# sheet1.net
KiCad netlist of a schematic drawn in Altium Designer
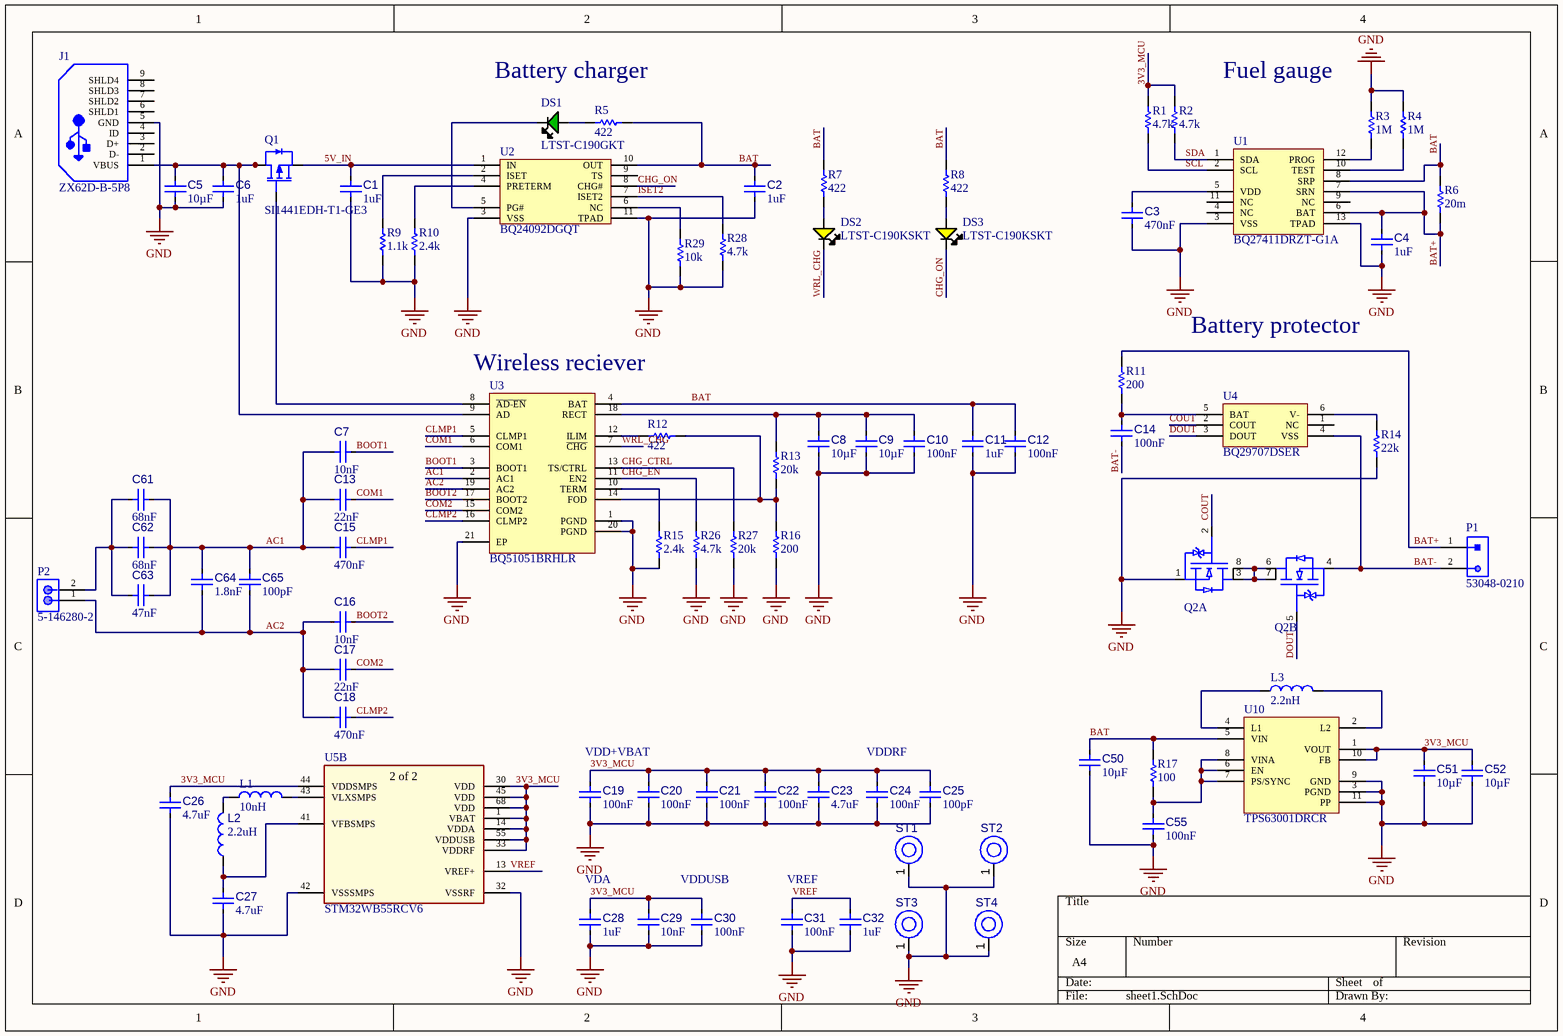
[diagram p0: sheet1.SchDoc]

(export (version "E")
  (design (tool "Eeschema 10.0.6"))
  (components
    (comp (ref "C1")
      (value "1uF")
      (footprint "0603-SMD-CAP")
      (fields
        (field (name "VOLTAGE") "25V")
        (field (name "TOLERANCE") "10%")
        (field (name "MFR. PART NO.") "C0603C105K3PACTU")
      )
      (libsource (lib "Budapest University of Technology and Economics") (part "CAP-NP-2"))
    )
    (comp (ref "C2")
      (value "1uF")
      (footprint "0603-SMD-CAP")
      (fields
        (field (name "VOLTAGE") "25V")
        (field (name "TOLERANCE") "10%")
        (field (name "MFR. PART NO.") "C0603C105K3PACTU")
      )
      (libsource (lib "Budapest University of Technology and Economics") (part "CAP-NP-2"))
    )
    (comp (ref "C3")
      (value "470nF")
      (footprint "CAPC0603(1608)100_L")
      (description "Chip Capacitor, 470nF +/-20%, 25V, 0603, Thickness 1 mm")
      (fields (field (name "TOLERANCE") "10%") (field (name "Comment") "Capacitor 470nF +/-20% 25V 0603"))
      (libsource (lib "Budapest University of Technology and Economics") (part "CAP-NP-2"))
    )
    (comp (ref "C4")
      (value "1uF")
      (footprint "0603-SMD-CAP")
      (fields
        (field (name "VOLTAGE") "25V")
        (field (name "TOLERANCE") "10%")
        (field (name "MFR. PART NO.") "C0603C105K3PACTU")
      )
      (libsource (lib "Budapest University of Technology and Economics") (part "CAP-NP-2"))
    )
    (comp (ref "C5")
      (value "10µF")
      (footprint "0603-SMD-CAP")
      (description "Chip Capacitor, 10µF +/-20%, 10V, 0603, Thickness 1 mm")
      (fields (field (name "TOLERANCE") "10%") (field (name "MFR. PART NO.") "0603ZD106KAT2A"))
      (libsource (lib "Budapest University of Technology and Economics") (part "CAP-NP-2"))
    )
    (comp (ref "C6")
      (value "1uF")
      (footprint "0603-SMD-CAP")
      (fields
        (field (name "VOLTAGE") "25V")
        (field (name "TOLERANCE") "10%")
        (field (name "MFR. PART NO.") "C0603C105K3PACTU")
      )
      (libsource (lib "Budapest University of Technology and Economics") (part "CAP-NP-2"))
    )
    (comp (ref "C7")
      (value "10nF")
      (footprint "0402-SMD-CAP")
      (description "Cap Ceramic 0.01uF 50V X7R 10% SMD 0402 125C Paper T/R")
      (fields (field (name "TOLERANCE") "10%") (field (name "VOLTAGE") "50V"))
      (libsource (lib "Budapest University of Technology and Economics") (part "CAP-NP-2"))
    )
    (comp (ref "C8")
      (value "10µF")
      (footprint "0603-SMD-CAP")
      (description "Chip Capacitor, 10µF +/-20%, 10V, 0603, Thickness 1 mm")
      (fields (field (name "TOLERANCE") "10%") (field (name "MFR. PART NO.") "0603ZD106KAT2A"))
      (libsource (lib "Budapest University of Technology and Economics") (part "CAP-NP-2"))
    )
    (comp (ref "C9")
      (value "10µF")
      (footprint "0603-SMD-CAP")
      (description "Chip Capacitor, 10µF +/-20%, 10V, 0603, Thickness 1 mm")
      (fields (field (name "TOLERANCE") "10%") (field (name "MFR. PART NO.") "0603ZD106KAT2A"))
      (libsource (lib "Budapest University of Technology and Economics") (part "CAP-NP-2"))
    )
    (comp (ref "C10")
      (value "100nF")
      (footprint "0402-SMD-CAP")
      (description "Chip Capacitor, 0.1 uF, +/- 5%, 16 V, 0402 (1005 Metric)")
      (fields (field (name "TOLERANCE") "5%") (field (name "MFR. PART NO.") "EMF105B7104MVHF"))
      (libsource (lib "Budapest University of Technology and Economics") (part "CAP-NP-2"))
    )
    (comp (ref "C11")
      (value "1uF")
      (footprint "0603-SMD-CAP")
      (fields
        (field (name "VOLTAGE") "25V")
        (field (name "TOLERANCE") "10%")
        (field (name "MFR. PART NO.") "C0603C105K3PACTU")
      )
      (libsource (lib "Budapest University of Technology and Economics") (part "CAP-NP-2"))
    )
    (comp (ref "C12")
      (value "100nF")
      (footprint "0402-SMD-CAP")
      (description "Chip Capacitor, 0.1 uF, +/- 5%, 16 V, 0402 (1005 Metric)")
      (fields (field (name "TOLERANCE") "5%") (field (name "MFR. PART NO.") "EMF105B7104MVHF"))
      (libsource (lib "Budapest University of Technology and Economics") (part "CAP-NP-2"))
    )
    (comp (ref "C13")
      (value "22nF")
      (footprint "0402-SMD-CAP")
      (description "0402 22 nF 25 V ±10 % Tolerance X7R SMT Multilayer Ceramic Capacitor")
      (fields (field (name "TOLERANCE") "10%") (field (name "MFR. PART NO.") "CC0402KRX7R8BB223"))
      (libsource (lib "Budapest University of Technology and Economics") (part "CAP-NP-2"))
    )
    (comp (ref "C14")
      (value "100nF")
      (footprint "0402-SMD-CAP")
      (description "Chip Capacitor, 0.1 uF, +/- 5%, 16 V, 0402 (1005 Metric)")
      (fields (field (name "TOLERANCE") "5%") (field (name "MFR. PART NO.") "EMF105B7104MVHF"))
      (libsource (lib "Budapest University of Technology and Economics") (part "CAP-NP-2"))
    )
    (comp (ref "C15")
      (value "470nF")
      (footprint "0402-SMD-CAP")
      (description "TDK         C1005X5R1E474K050BB            CERAMIC CAPACITOR, 0.47UF, 25V, X5R, 0402")
      (fields (field (name "MFR. PART NO.") "C1005X5R1E474K050BB") (field (name "VOLTAGE") "25V"))
      (libsource (lib "Budapest University of Technology and Economics") (part "CAP-NP-2"))
    )
    (comp (ref "C16")
      (value "10nF")
      (footprint "0402-SMD-CAP")
      (description "Cap Ceramic 0.01uF 50V X7R 10% SMD 0402 125C Paper T/R")
      (fields (field (name "TOLERANCE") "10%") (field (name "VOLTAGE") "50V"))
      (libsource (lib "Budapest University of Technology and Economics") (part "CAP-NP-2"))
    )
    (comp (ref "C17")
      (value "22nF")
      (footprint "0402-SMD-CAP")
      (description "0402 22 nF 25 V ±10 % Tolerance X7R SMT Multilayer Ceramic Capacitor")
      (fields (field (name "TOLERANCE") "10%") (field (name "MFR. PART NO.") "CC0402KRX7R8BB223"))
      (libsource (lib "Budapest University of Technology and Economics") (part "CAP-NP-2"))
    )
    (comp (ref "C18")
      (value "470nF")
      (footprint "0402-SMD-CAP")
      (description "TDK         C1005X5R1E474K050BB            CERAMIC CAPACITOR, 0.47UF, 25V, X5R, 0402")
      (fields (field (name "MFR. PART NO.") "C1005X5R1E474K050BB") (field (name "VOLTAGE") "25V"))
      (libsource (lib "Budapest University of Technology and Economics") (part "CAP-NP-2"))
    )
    (comp (ref "C19")
      (value "100nF")
      (footprint "0402-SMD-CAP")
      (description "Chip Capacitor, 0.1 uF, +/- 5%, 16 V, 0402 (1005 Metric)")
      (fields (field (name "TOLERANCE") "5%") (field (name "MFR. PART NO.") "EMF105B7104MVHF"))
      (libsource (lib "Budapest University of Technology and Economics") (part "CAP-NP-2"))
    )
    (comp (ref "C20")
      (value "100nF")
      (footprint "0402-SMD-CAP")
      (description "Chip Capacitor, 0.1 uF, +/- 5%, 16 V, 0402 (1005 Metric)")
      (fields (field (name "TOLERANCE") "5%") (field (name "MFR. PART NO.") "EMF105B7104MVHF"))
      (libsource (lib "Budapest University of Technology and Economics") (part "CAP-NP-2"))
    )
    (comp (ref "C21")
      (value "100nF")
      (footprint "0402-SMD-CAP")
      (description "Chip Capacitor, 0.1 uF, +/- 5%, 16 V, 0402 (1005 Metric)")
      (fields (field (name "TOLERANCE") "5%") (field (name "MFR. PART NO.") "EMF105B7104MVHF"))
      (libsource (lib "Budapest University of Technology and Economics") (part "CAP-NP-2"))
    )
    (comp (ref "C22")
      (value "100nF")
      (footprint "0402-SMD-CAP")
      (description "Chip Capacitor, 0.1 uF, +/- 5%, 16 V, 0402 (1005 Metric)")
      (fields (field (name "TOLERANCE") "5%") (field (name "MFR. PART NO.") "EMF105B7104MVHF"))
      (libsource (lib "Budapest University of Technology and Economics") (part "CAP-NP-2"))
    )
    (comp (ref "C23")
      (value "4.7uF")
      (footprint "0603-SMD-CAP")
      (fields
        (field (name "TOLERANCE") "10%")
        (field (name "VOLTAGE") "6.3V")
        (field (name "Comment") "C0603C475K9PACTU")
      )
      (libsource (lib "Budapest University of Technology and Economics") (part "CAP-NP-2"))
    )
    (comp (ref "C24")
      (value "100nF")
      (footprint "0402-SMD-CAP")
      (description "Chip Capacitor, 0.1 uF, +/- 5%, 16 V, 0402 (1005 Metric)")
      (fields (field (name "TOLERANCE") "5%") (field (name "MFR. PART NO.") "EMF105B7104MVHF"))
      (libsource (lib "Budapest University of Technology and Economics") (part "CAP-NP-2"))
    )
    (comp (ref "C25")
      (value "100pF")
      (footprint "0402-SMD-CAP")
      (description "Capacitor, Ceramic; 100pf; Chip; Case 0402; Npo; +/-5%; 50wvdc; Smd; 2.5% Df; Tr")
      (fields (field (name "VOLTAGE") "50V") (field (name "TOLERANCE") "5%"))
      (libsource (lib "Budapest University of Technology and Economics") (part "CAP-NP-2"))
    )
    (comp (ref "C26")
      (value "4.7uF")
      (footprint "0603-SMD-CAP")
      (fields
        (field (name "TOLERANCE") "10%")
        (field (name "VOLTAGE") "6.3V")
        (field (name "Comment") "C0603C475K9PACTU")
      )
      (libsource (lib "Budapest University of Technology and Economics") (part "CAP-NP-2"))
    )
    (comp (ref "C27")
      (value "4.7uF")
      (footprint "0603-SMD-CAP")
      (fields
        (field (name "TOLERANCE") "10%")
        (field (name "VOLTAGE") "6.3V")
        (field (name "Comment") "C0603C475K9PACTU")
      )
      (libsource (lib "Budapest University of Technology and Economics") (part "CAP-NP-2"))
    )
    (comp (ref "C28")
      (value "1uF")
      (footprint "0603-SMD-CAP")
      (fields
        (field (name "VOLTAGE") "25V")
        (field (name "TOLERANCE") "10%")
        (field (name "MFR. PART NO.") "C0603C105K3PACTU")
      )
      (libsource (lib "Budapest University of Technology and Economics") (part "CAP-NP-2"))
    )
    (comp (ref "C29")
      (value "10nF")
      (footprint "0402-SMD-CAP")
      (description "CAP CER 10000PF 16V X7R 0402")
      (fields (field (name "MFR. PART NO.") "CC0402KRX7R7BB103") (field (name "TOLERANCE") "10%"))
      (libsource (lib "Budapest University of Technology and Economics") (part "CAP-NP-2"))
    )
    (comp (ref "C30")
      (value "100nF")
      (footprint "0402-SMD-CAP")
      (description "Chip Capacitor, 0.1 uF, +/- 5%, 16 V, 0402 (1005 Metric)")
      (fields (field (name "TOLERANCE") "5%") (field (name "MFR. PART NO.") "EMF105B7104MVHF"))
      (libsource (lib "Budapest University of Technology and Economics") (part "CAP-NP-2"))
    )
    (comp (ref "C31")
      (value "100nF")
      (footprint "0402-SMD-CAP")
      (description "Chip Capacitor, 0.1 uF, +/- 5%, 16 V, 0402 (1005 Metric)")
      (fields (field (name "TOLERANCE") "5%") (field (name "MFR. PART NO.") "EMF105B7104MVHF"))
      (libsource (lib "Budapest University of Technology and Economics") (part "CAP-NP-2"))
    )
    (comp (ref "C32")
      (value "1uF")
      (footprint "0603-SMD-CAP")
      (fields
        (field (name "VOLTAGE") "25V")
        (field (name "TOLERANCE") "10%")
        (field (name "MFR. PART NO.") "C0603C105K3PACTU")
      )
      (libsource (lib "Budapest University of Technology and Economics") (part "CAP-NP-2"))
    )
    (comp (ref "C50")
      (value "10µF")
      (footprint "0603-SMD-CAP")
      (description "Chip Capacitor, 10µF +/-20%, 10V, 0603, Thickness 1 mm")
      (fields (field (name "TOLERANCE") "10%") (field (name "MFR. PART NO.") "0603ZD106KAT2A"))
      (libsource (lib "Budapest University of Technology and Economics") (part "CAP-NP-2"))
    )
    (comp (ref "C51")
      (value "10µF")
      (footprint "0603-SMD-CAP")
      (description "Chip Capacitor, 10µF +/-20%, 10V, 0603, Thickness 1 mm")
      (fields (field (name "TOLERANCE") "10%") (field (name "MFR. PART NO.") "0603ZD106KAT2A"))
      (libsource (lib "Budapest University of Technology and Economics") (part "CAP-NP-2"))
    )
    (comp (ref "C52")
      (value "10µF")
      (footprint "0603-SMD-CAP")
      (description "Chip Capacitor, 10µF +/-20%, 10V, 0603, Thickness 1 mm")
      (fields (field (name "TOLERANCE") "10%") (field (name "MFR. PART NO.") "0603ZD106KAT2A"))
      (libsource (lib "Budapest University of Technology and Economics") (part "CAP-NP-2"))
    )
    (comp (ref "C55")
      (value "100nF")
      (footprint "0402-SMD-CAP")
      (description "Chip Capacitor, 0.1 uF, +/- 5%, 16 V, 0402 (1005 Metric)")
      (fields (field (name "TOLERANCE") "5%") (field (name "MFR. PART NO.") "EMF105B7104MVHF"))
      (libsource (lib "Budapest University of Technology and Economics") (part "CAP-NP-2"))
    )
    (comp (ref "C61")
      (value "68nF")
      (footprint "0603-SMD-CAP")
      (description "Cap Ceramic 0.068uF 50V X7R 10% SMD 0603 125C Paper T/R")
      (fields (field (name "VOLTAGE") "50V") (field (name "TOLERANCE") "10%"))
      (libsource (lib "Budapest University of Technology and Economics") (part "CAP-NP-2"))
    )
    (comp (ref "C62")
      (value "68nF")
      (footprint "0603-SMD-CAP")
      (description "Cap Ceramic 0.068uF 50V X7R 10% SMD 0603 125C Paper T/R")
      (fields (field (name "VOLTAGE") "50V") (field (name "TOLERANCE") "10%"))
      (libsource (lib "Budapest University of Technology and Economics") (part "CAP-NP-2"))
    )
    (comp (ref "C63")
      (value "47nF")
      (footprint "0603-SMD-CAP")
      (fields
        (field (name "VOLTAGE") "50V")
        (field (name "TOLERANCE") "80%")
        (field (name "MFR. PART NO.") "06035G473ZAT2A")
      )
      (libsource (lib "Budapest University of Technology and Economics") (part "CAP-NP-2"))
    )
    (comp (ref "C64")
      (value "1.8nF")
      (footprint "0603-SMD-CAP")
      (fields (field (name "MFR PART NO.") "06031C182JAT2A") (field (name "TOLERANCE") "5%"))
      (libsource (lib "Budapest University of Technology and Economics") (part "CAP-NP-2"))
    )
    (comp (ref "C65")
      (value "100pF")
      (footprint "0402-SMD-CAP")
      (description "Capacitor, Ceramic; 100pf; Chip; Case 0402; Npo; +/-5%; 50wvdc; Smd; 2.5% Df; Tr")
      (fields (field (name "VOLTAGE") "50V") (field (name "TOLERANCE") "5%"))
      (libsource (lib "Budapest University of Technology and Economics") (part "CAP-NP-2"))
    )
    (comp (ref "DS1")
      (value "LTST-C190GKT")
      (footprint "LTST-C190GKT_V")
      (description "LED Uni-Color Green, 100 mW, 30 mA, -55 to 85 degC, 2-Pin SMD, RoHS, Tape and Reel")
      (fields (field (name "POWER") "100mW") (field (name "MANUFACTURER") "Lite-On"))
      (libsource (lib "Budapest University of Technology and Economics") (part "LED-GREEN-AK-2"))
    )
    (comp (ref "DS2")
      (value "LTST-C190KSKT")
      (footprint "LTST-C190KSKT_V")
      (description "LED Uni-Color Yellow, 75 mW, 30 mA, -30 to 85 degC, 2-Pin SMD, RoHS, Tape and Reel")
      (fields (field (name "MANUFACTURER") "Lite-On") (field (name "POWER") "75mW"))
      (libsource (lib "Budapest University of Technology and Economics") (part "LED-YELLOW-AK-2"))
    )
    (comp (ref "DS3")
      (value "LTST-C190KSKT")
      (footprint "LTST-C190KSKT_V")
      (description "LED Uni-Color Yellow, 75 mW, 30 mA, -30 to 85 degC, 2-Pin SMD, RoHS, Tape and Reel")
      (fields (field (name "MANUFACTURER") "Lite-On") (field (name "POWER") "75mW"))
      (libsource (lib "Budapest University of Technology and Economics") (part "LED-YELLOW-AK-2"))
    )
    (comp (ref "J1")
      (value "ZX62D-B-5P8")
      (footprint "HIRO-ZX62D-B-5P8_V")
      (fields (field (name "MANUFACTURER") "Hirose Electric"))
      (libsource (lib "Budapest University of Technology and Economics") (part "USB-5-4SHLD"))
    )
    (comp (ref "L1")
      (value "10nH")
      (footprint "0603-SMD-IND")
      (description "EPCOS   B82496C3100J   INDUCTOR, 0603 CASE, 10NH")
      (fields (field (name "TOLERANCE") "5%") (field (name "MFR. PART NO.") "B82496C3100J000"))
      (libsource (lib "Budapest University of Technology and Economics") (part "IND-2"))
    )
    (comp (ref "L2")
      (value "2.2uH")
      (footprint "0603-SMD-IND")
      (description "Inductor Power Shielded Multi-Layer 2.2uH 20% 1MHz Ferrite 0.75A 0.3Ohm DCR 0603 T/R")
      (fields (field (name "MFR. PART NO.") "CVH160808-2R2M"))
      (libsource (lib "Budapest University of Technology and Economics") (part "IND-2"))
    )
    (comp (ref "L3")
      (value "2.2nH")
      (footprint "0603-SMD-IND")
      (description "2.2nH Unshielded Wirewound Inductor 1.5A 35 mOhm Max 0603 (1608 Metric)")
      (fields (field (name "MFR. PART NO.") "B82496C3229A"))
      (libsource (lib "Budapest University of Technology and Economics") (part "IND-2"))
    )
    (comp (ref "P1")
      (value "53048-0210")
      (footprint "PHOE-1803277_V")
      (libsource (lib "Budapest University of Technology and Economics") (part "53048-0210"))
    )
    (comp (ref "P2")
      (value "5-146280-2")
      (footprint "TECO-5-146280-2_V")
      (description "AMPMODU 2 Position 2.54 mm Single Row Through-Hole Straight Breakaway Header")
      (libsource (lib "Budapest University of Technology and Economics") (part "CN-1P-M-R2"))
    )
    (comp (ref "Q1")
      (value "SI1441EDH-T1-GE3")
      (footprint "SOT23127P600-8N")
      (description "MOSFET -20V 41mOhm@4.5V 4A P-Ch G-III")
      (libsource (lib "Budapest University of Technology and Economics") (part "SI1441EDH-T1-GE3"))
    )
    (comp (ref "Q2")
      (value "CSD85301Q2")
      (footprint "SON65P200X80_HS-7N")
      (description "MOSFET 2N-CH 20V 5A 6WSON")
      (libsource (lib "Budapest University of Technology and Economics") (part "CSD85301Q2"))
    )
    (comp (ref "R1")
      (value "4.7k")
      (footprint "0603-SMD-RES")
      (description "RESISTOR, 0603, 0.1W, 1%, 4K7")
      (fields (field (name "TOLERANCE") "1%") (field (name "Comment") "ERJ-3EKF4701V"))
      (libsource (lib "Budapest University of Technology and Economics") (part "RES-2"))
    )
    (comp (ref "R2")
      (value "4.7k")
      (footprint "0603-SMD-RES")
      (description "RESISTOR, 0603, 0.1W, 1%, 4K7")
      (fields (field (name "TOLERANCE") "1%") (field (name "Comment") "ERJ-3EKF4701V"))
      (libsource (lib "Budapest University of Technology and Economics") (part "RES-2"))
    )
    (comp (ref "R3")
      (value "1M")
      (footprint "0603-SMD-RES")
      (description "Res Thick Film 0603 1M Ohm 5% 1/10W ±200ppm/C Molded SMD SMD Paper Tape on Plastic Reel")
      (fields (field (name "MFR. PART NO.") "CR0603-JW-105ELF") (field (name "TOLERANCE") "5%"))
      (libsource (lib "Budapest University of Technology and Economics") (part "RES-2"))
    )
    (comp (ref "R4")
      (value "1M")
      (footprint "0603-SMD-RES")
      (description "Res Thick Film 0603 1M Ohm 5% 1/10W ±200ppm/C Molded SMD SMD Paper Tape on Plastic Reel")
      (fields (field (name "MFR. PART NO.") "CR0603-JW-105ELF") (field (name "TOLERANCE") "5%"))
      (libsource (lib "Budapest University of Technology and Economics") (part "RES-2"))
    )
    (comp (ref "R5")
      (value "422")
      (footprint "0402_SMD_RES")
      (description "Res Thick Film 0402 422 Ohm 1% 0.1W(1/10W) ±100ppm/C Molded SMD Automotive Punched T/R")
      (fields (field (name "MFR. PART NO.") "ERJ-2RKF4220X") (field (name "TOLERANCE") "1%"))
      (libsource (lib "Budapest University of Technology and Economics") (part "RES-2"))
    )
    (comp (ref "R6")
      (value "20m")
      (footprint "Chip2PinSM127P600-8N")
      (description "Res Metal Strip 1206 0.02 Ohm 1% 1W 75ppm/C Molded SMD SMD T/R")
      (fields (field (name "MFR. PART NO.") "WSLP1206R0200FEA") (field (name "TOLERANCE") "1%"))
      (libsource (lib "Budapest University of Technology and Economics") (part "RES-2"))
    )
    (comp (ref "R7")
      (value "422")
      (footprint "0402_SMD_RES")
      (description "Res Thick Film 0402 422 Ohm 1% 0.1W(1/10W) ±100ppm/C Molded SMD Automotive Punched T/R")
      (fields (field (name "MFR. PART NO.") "ERJ-2RKF4220X") (field (name "TOLERANCE") "1%"))
      (libsource (lib "Budapest University of Technology and Economics") (part "RES-2"))
    )
    (comp (ref "R8")
      (value "422")
      (footprint "0402_SMD_RES")
      (description "Res Thick Film 0402 422 Ohm 1% 0.1W(1/10W) ±100ppm/C Molded SMD Automotive Punched T/R")
      (fields (field (name "MFR. PART NO.") "ERJ-2RKF4220X") (field (name "TOLERANCE") "1%"))
      (libsource (lib "Budapest University of Technology and Economics") (part "RES-2"))
    )
    (comp (ref "R9")
      (value "1.1k")
      (footprint "0603-SMD-RES")
      (description "Resistor, Thick Film; 1.1 Kilohms; 0.10 W @   degC; + 1%; 75 V; 0603; -55  degC")
      (fields (field (name "MFR. PART NO.") "CRCW06031K10FKEA") (field (name "TOLERANCE") "1%"))
      (libsource (lib "Budapest University of Technology and Economics") (part "RES-2"))
    )
    (comp (ref "R10")
      (value "2.4k")
      (footprint "0603-SMD-RES")
      (description "Res Thick Film 0603 2.4K Ohm 1% 0.1W(1/10W) }100ppm/C Molded SMD Automotive Punched T/R")
      (fields (field (name "MFR. PART NO.") "ERJ-3EKF2401V") (field (name "TOLERANCE") "1%"))
      (libsource (lib "Budapest University of Technology and Economics") (part "RES-2"))
    )
    (comp (ref "R11")
      (value "200")
      (footprint "0402_SMD_RES")
      (description "SMD Chip Resistor, 0402 [1005 Metric], 200 ohm, CRCW e3 Series, 50 V, Thick Film, 63 mW")
      (fields (field (name "TOLERANCE") "1%") (field (name "MFR. PART NO.") "CRCW0402200RFKED"))
      (libsource (lib "Budapest University of Technology and Economics") (part "RES-2"))
    )
    (comp (ref "R12")
      (value "422")
      (footprint "0402_SMD_RES")
      (description "Res Thick Film 0402 422 Ohm 1% 0.1W(1/10W) ±100ppm/C Molded SMD Automotive Punched T/R")
      (fields (field (name "MFR. PART NO.") "ERJ-2RKF4220X") (field (name "TOLERANCE") "1%"))
      (libsource (lib "Budapest University of Technology and Economics") (part "RES-2"))
    )
    (comp (ref "R13")
      (value "20k")
      (footprint "0402_SMD_RES")
      (description "RES SMD 20K OHM 1% 1/16W 0402")
      (fields (field (name "TOLERANCE") "1%") (field (name "MFR. PART NO.") "CRCW040220K0FKED"))
      (libsource (lib "Budapest University of Technology and Economics") (part "RES-2"))
    )
    (comp (ref "R14")
      (value "22k")
      (footprint "0603-SMD-RES")
      (fields (field (name "TOLERANCE") "1%") (field (name "Comment") "CRCW060322K0FKEA"))
      (libsource (lib "Budapest University of Technology and Economics") (part "RES-2"))
    )
    (comp (ref "R15")
      (value "2.4k")
      (footprint "0603-SMD-RES")
      (description "Res Thick Film 0603 2.4K Ohm 1% 0.1W(1/10W) }100ppm/C Molded SMD Automotive Punched T/R")
      (fields (field (name "MFR. PART NO.") "ERJ-3EKF2401V") (field (name "TOLERANCE") "1%"))
      (libsource (lib "Budapest University of Technology and Economics") (part "RES-2"))
    )
    (comp (ref "R16")
      (value "200")
      (footprint "0402_SMD_RES")
      (description "SMD Chip Resistor, 0402 [1005 Metric], 200 ohm, CRCW e3 Series, 50 V, Thick Film, 63 mW")
      (fields (field (name "TOLERANCE") "1%") (field (name "MFR. PART NO.") "CRCW0402200RFKED"))
      (libsource (lib "Budapest University of Technology and Economics") (part "RES-2"))
    )
    (comp (ref "R17")
      (value "100")
      (footprint "0603-SMD-RES")
      (description "Res Thick Film 0603 100 Ohm 1% 1/10W ±100ppm/°C Molded SMD Paper T/R")
      (fields (field (name "TOLERANCE") "1%") (field (name "MFR. PART NO.") "CRCW0603100RFKEA"))
      (libsource (lib "Budapest University of Technology and Economics") (part "RES-2"))
    )
    (comp (ref "R26")
      (value "4.7k")
      (footprint "0603-SMD-RES")
      (description "RESISTOR, 0603, 0.1W, 1%, 4K7")
      (fields (field (name "TOLERANCE") "1%") (field (name "Comment") "ERJ-3EKF4701V"))
      (libsource (lib "Budapest University of Technology and Economics") (part "RES-2"))
    )
    (comp (ref "R27")
      (value "20k")
      (footprint "0603-SMD-RES")
      (fields (field (name "TOLERANCE") "1%") (field (name "Comment") "CRCW060320K0FKEA"))
      (libsource (lib "Budapest University of Technology and Economics") (part "RES-2"))
    )
    (comp (ref "R28")
      (value "4.7k")
      (footprint "0603-SMD-RES")
      (description "RESISTOR, 0603, 0.1W, 1%, 4K7")
      (fields (field (name "TOLERANCE") "1%") (field (name "Comment") "ERJ-3EKF4701V"))
      (libsource (lib "Budapest University of Technology and Economics") (part "RES-2"))
    )
    (comp (ref "R29")
      (value "10k")
      (footprint "0402_SMD_RES")
      (description "Chip Resistor, 10 kOhms, +/-1 %, 63 mW, -55 to 125 degC, 0402")
      (fields (field (name "POWER") "63mW") (field (name "MFR. PART NO.") "CRCW040210K0FKTD"))
      (libsource (lib "Budapest University of Technology and Economics") (part "RES-2"))
    )
    (comp (ref "ST1")
      (value "PTH-M2D5X5")
      (footprint "PTH-M2D5X5")
      (description "M2 PTH (2.5mm), 5mm pad")
      (libsource (lib "Budapest University of Technology and Economics") (part "CMP-00028-00000-1"))
    )
    (comp (ref "ST2")
      (value "PTH-M2D5X5")
      (footprint "PTH-M2D5X5")
      (description "M2 PTH (2.5mm), 5mm pad")
      (libsource (lib "Budapest University of Technology and Economics") (part "CMP-00028-00000-1"))
    )
    (comp (ref "ST3")
      (value "PTH-M2D5X5")
      (footprint "PTH-M2D5X5")
      (description "M2 PTH (2.5mm), 5mm pad")
      (libsource (lib "Budapest University of Technology and Economics") (part "CMP-00028-00000-1"))
    )
    (comp (ref "ST4")
      (value "PTH-M2D5X5")
      (footprint "PTH-M2D5X5")
      (description "M2 PTH (2.5mm), 5mm pad")
      (libsource (lib "Budapest University of Technology and Economics") (part "CMP-00028-00000-1"))
    )
    (comp (ref "U1")
      (value "BQ27411DRZT-G1A")
      (footprint "SON40P400X100_HS-13N")
      (description "IC BATT FUEL GAUGE LICOO2 12SON")
      (libsource (lib "Budapest University of Technology and Economics") (part "BQ27411DRZT-G1A"))
    )
    (comp (ref "U2")
      (value "BQ24092DGQT")
      (footprint "TSSOP50P490X110_HS-11L")
      (description "Battery Charger Li-Ion/Li-Pol 1000mA 4.2V 10-Pin MSOP EP T/R")
      (libsource (lib "Budapest University of Technology and Economics") (part "BQ24092DGQT"))
    )
    (comp (ref "U3")
      (value "BQ51051BRHLR")
      (footprint "RHL0020A_V")
      (description "IC WIRELESS PWR RCVR 20QFN")
      (libsource (lib "Budapest University of Technology and Economics") (part "BQ51051BRHLR"))
    )
    (comp (ref "U4")
      (value "BQ29707DSER")
      (footprint "SON50P150X80-6N")
      (description "IC LITHIUM BATT PROTECT 6WSON")
      (libsource (lib "Budapest University of Technology and Economics") (part "BQ29707DSER"))
    )
    (comp (ref "U5")
      (value "STM32WB55RCV6")
      (footprint "QFN40P800X800X100_HS-69N")
      (fields (field (name "MANUFACTURER") "ST"))
      (libsource (lib "Budapest University of Technology and Economics") (part "STM32WB55RCV6"))
    )
    (comp (ref "U10")
      (value "TPS63001DRCR")
      (footprint "DRC0010J_V")
      (description "TEXAS INSTRUMENTS         TPS63001DRCR             CONVERTER, BUCK-BOOST, SON-10, FULL REEL")
      (libsource (lib "Budapest University of Technology and Economics") (part "TPS63001DRCR"))
    )
  )
  (nets
    (net (code "1") (name "/3V3_MCU") (class "Default")
      (node (ref "C19") (pin "1") (pinfunction "1_1") (pintype "passive"))
      (node (ref "C20") (pin "1") (pinfunction "1_1") (pintype "passive"))
      (node (ref "C21") (pin "1") (pinfunction "1_1") (pintype "passive"))
      (node (ref "C22") (pin "1") (pinfunction "1_1") (pintype "passive"))
      (node (ref "C23") (pin "1") (pinfunction "1_1") (pintype "passive"))
      (node (ref "C24") (pin "1") (pinfunction "1_1") (pintype "passive"))
      (node (ref "C25") (pin "1") (pinfunction "1_1") (pintype "passive"))
      (node (ref "C26") (pin "1") (pinfunction "1_1") (pintype "passive"))
      (node (ref "C28") (pin "1") (pinfunction "1_1") (pintype "passive"))
      (node (ref "C29") (pin "1") (pinfunction "1_1") (pintype "passive"))
      (node (ref "C30") (pin "1") (pinfunction "1_1") (pintype "passive"))
      (node (ref "C51") (pin "2") (pinfunction "2_2") (pintype "passive"))
      (node (ref "C52") (pin "2") (pinfunction "2_2") (pintype "passive"))
      (node (ref "R1") (pin "2") (pinfunction "2_2") (pintype "passive"))
      (node (ref "R2") (pin "2") (pinfunction "2_2") (pintype "passive"))
      (node (ref "U10") (pin "1") (pinfunction "VOUT_1") (pintype "power_in"))
      (node (ref "U10") (pin "10") (pinfunction "FB_10") (pintype "passive"))
      (node (ref "U5") (pin "1") (pinfunction "VBAT_1") (pintype "power_in"))
      (node (ref "U5") (pin "14") (pinfunction "VDDA_14") (pintype "power_in"))
      (node (ref "U5") (pin "30") (pinfunction "VDD_30") (pintype "power_in"))
      (node (ref "U5") (pin "33") (pinfunction "VDDRF_33") (pintype "power_in"))
      (node (ref "U5") (pin "44") (pinfunction "VDDSMPS_44") (pintype "power_in"))
      (node (ref "U5") (pin "45") (pinfunction "VDD_45") (pintype "power_in"))
      (node (ref "U5") (pin "55") (pinfunction "VDDUSB_55") (pintype "power_in"))
      (node (ref "U5") (pin "68") (pinfunction "VDD_68") (pintype "power_in"))
    )
    (net (code "2") (name "/5V_IN") (class "Default")
      (node (ref "C1") (pin "1") (pinfunction "1_1") (pintype "passive"))
      (node (ref "Q1") (pin "4") (pinfunction "SOURCE_4") (pintype "passive"))
      (node (ref "U2") (pin "1") (pinfunction "IN_1") (pintype "passive"))
    )
    (net (code "3") (name "/AC1") (class "Default")
      (node (ref "C13") (pin "1") (pinfunction "1_1") (pintype "passive"))
      (node (ref "C15") (pin "1") (pinfunction "1_1") (pintype "passive"))
      (node (ref "C61") (pin "2") (pinfunction "2_2") (pintype "passive"))
      (node (ref "C62") (pin "2") (pinfunction "2_2") (pintype "passive"))
      (node (ref "C63") (pin "2") (pinfunction "2_2") (pintype "passive"))
      (node (ref "C64") (pin "1") (pinfunction "1_1") (pintype "passive"))
      (node (ref "C65") (pin "1") (pinfunction "1_1") (pintype "passive"))
      (node (ref "C7") (pin "1") (pinfunction "1_1") (pintype "passive"))
      (node (ref "U3") (pin "2") (pinfunction "AC1_2") (pintype "power_in"))
    )
    (net (code "4") (name "/AC2") (class "Default")
      (node (ref "C16") (pin "1") (pinfunction "1_1") (pintype "passive"))
      (node (ref "C17") (pin "1") (pinfunction "1_1") (pintype "passive"))
      (node (ref "C18") (pin "1") (pinfunction "1_1") (pintype "passive"))
      (node (ref "C64") (pin "2") (pinfunction "2_2") (pintype "passive"))
      (node (ref "C65") (pin "2") (pinfunction "2_2") (pintype "passive"))
      (node (ref "P2") (pin "1") (pinfunction "1_1") (pintype "passive"))
      (node (ref "U3") (pin "19") (pinfunction "AC2_19") (pintype "power_in"))
    )
    (net (code "5") (name "/BAT") (class "Default")
      (node (ref "C11") (pin "1") (pinfunction "1_1") (pintype "passive"))
      (node (ref "C12") (pin "1") (pinfunction "1_1") (pintype "passive"))
      (node (ref "C2") (pin "1") (pinfunction "1_1") (pintype "passive"))
      (node (ref "C50") (pin "2") (pinfunction "2_2") (pintype "passive"))
      (node (ref "R17") (pin "2") (pinfunction "2_2") (pintype "passive"))
      (node (ref "R5") (pin "1") (pinfunction "1_1") (pintype "passive"))
      (node (ref "R6") (pin "2") (pinfunction "2_2") (pintype "passive"))
      (node (ref "R7") (pin "2") (pinfunction "2_2") (pintype "passive"))
      (node (ref "R8") (pin "2") (pinfunction "2_2") (pintype "passive"))
      (node (ref "U1") (pin "8") (pinfunction "SRP_8") (pintype "passive"))
      (node (ref "U10") (pin "5") (pinfunction "VIN_5") (pintype "power_in"))
      (node (ref "U2") (pin "10") (pinfunction "OUT_10") (pintype "passive"))
      (node (ref "U3") (pin "4") (pinfunction "BAT_4") (pintype "power_in"))
    )
    (net (code "6") (name "/BAT+") (class "Default")
      (node (ref "C4") (pin "1") (pinfunction "1_1") (pintype "passive"))
      (node (ref "P1") (pin "1") (pinfunction "1_1") (pintype "passive"))
      (node (ref "R11") (pin "2") (pinfunction "2_2") (pintype "passive"))
      (node (ref "R6") (pin "1") (pinfunction "1_1") (pintype "passive"))
      (node (ref "U1") (pin "6") (pinfunction "BAT_6") (pintype "passive"))
      (node (ref "U1") (pin "7") (pinfunction "SRN_7") (pintype "passive"))
    )
    (net (code "7") (name "/BAT-") (class "Default")
      (node (ref "C14") (pin "2") (pinfunction "2_2") (pintype "passive"))
      (node (ref "P1") (pin "2") (pinfunction "2_2") (pintype "passive"))
      (node (ref "Q2") (pin "4") (pinfunction "S_4") (pintype "passive"))
      (node (ref "U4") (pin "4") (pinfunction "VSS_4") (pintype "passive"))
    )
    (net (code "8") (name "/BOOT1") (class "Default")
      (node (ref "C7") (pin "2") (pinfunction "2_2") (pintype "passive"))
      (node (ref "U3") (pin "3") (pinfunction "BOOT1_3") (pintype "passive"))
    )
    (net (code "9") (name "/BOOT2") (class "Default")
      (node (ref "C16") (pin "2") (pinfunction "2_2") (pintype "passive"))
      (node (ref "U3") (pin "17") (pinfunction "BOOT2_17") (pintype "passive"))
    )
    (net (code "10") (name "/CHG_CTRL") (class "Default")
      (node (ref "R27") (pin "2") (pinfunction "2_2") (pintype "passive"))
      (node (ref "U3") (pin "13") (pinfunction "TS/CTRL_13") (pintype "passive"))
    )
    (net (code "11") (name "/CHG_EN") (class "Default")
      (node (ref "R26") (pin "2") (pinfunction "2_2") (pintype "passive"))
      (node (ref "U3") (pin "11") (pinfunction "EN2_11") (pintype "passive"))
    )
    (net (code "12") (name "/CHG_ON") (class "Default")
      (node (ref "DS3") (pin "2") (pinfunction "K_2") (pintype "passive"))
      (node (ref "U2") (pin "8") (pinfunction "CHG#_8") (pintype "passive"))
    )
    (net (code "13") (name "/CLMP1") (class "Default")
      (node (ref "C15") (pin "2") (pinfunction "2_2") (pintype "passive"))
      (node (ref "U3") (pin "5") (pinfunction "CLMP1_5") (pintype "open_collector"))
    )
    (net (code "14") (name "/CLMP2") (class "Default")
      (node (ref "C18") (pin "2") (pinfunction "2_2") (pintype "passive"))
      (node (ref "U3") (pin "16") (pinfunction "CLMP2_16") (pintype "open_collector"))
    )
    (net (code "15") (name "/COM1") (class "Default")
      (node (ref "C13") (pin "2") (pinfunction "2_2") (pintype "passive"))
      (node (ref "U3") (pin "6") (pinfunction "COM1_6") (pintype "open_collector"))
    )
    (net (code "16") (name "/COM2") (class "Default")
      (node (ref "C17") (pin "2") (pinfunction "2_2") (pintype "passive"))
      (node (ref "U3") (pin "15") (pinfunction "COM2_15") (pintype "open_collector"))
    )
    (net (code "17") (name "/COUT") (class "Default")
      (node (ref "Q2") (pin "2") (pinfunction "G_2") (pintype "passive"))
      (node (ref "U4") (pin "2") (pinfunction "COUT_2") (pintype "passive"))
    )
    (net (code "18") (name "/DOUT") (class "Default")
      (node (ref "Q2") (pin "5") (pinfunction "G_5") (pintype "passive"))
      (node (ref "U4") (pin "3") (pinfunction "DOUT_3") (pintype "passive"))
    )
    (net (code "19") (name "/ISET2") (class "Default")
      (node (ref "R28") (pin "2") (pinfunction "2_2") (pintype "passive"))
      (node (ref "U2") (pin "7") (pinfunction "ISET2_7") (pintype "passive"))
    )
    (net (code "20") (name "/SCL") (class "Default")
      (node (ref "R1") (pin "1") (pinfunction "1_1") (pintype "passive"))
      (node (ref "U1") (pin "2") (pinfunction "SCL_2") (pintype "passive"))
    )
    (net (code "21") (name "/SDA") (class "Default")
      (node (ref "R2") (pin "1") (pinfunction "1_1") (pintype "passive"))
      (node (ref "U1") (pin "1") (pinfunction "SDA_1") (pintype "passive"))
    )
    (net (code "22") (name "/VREF") (class "Default")
      (node (ref "C31") (pin "1") (pinfunction "1_1") (pintype "passive"))
      (node (ref "C32") (pin "1") (pinfunction "1_1") (pintype "passive"))
      (node (ref "U5") (pin "13") (pinfunction "VREF+_13") (pintype "power_in"))
    )
    (net (code "23") (name "/WRL_CHG") (class "Default")
      (node (ref "DS2") (pin "2") (pinfunction "K_2") (pintype "passive"))
      (node (ref "U3") (pin "7") (pinfunction "~{CHG}_7") (pintype "open_collector"))
    )
    (net (code "24") (name "GND") (class "Default")
      (node (ref "C1") (pin "2") (pinfunction "2_2") (pintype "passive"))
      (node (ref "C10") (pin "2") (pinfunction "2_2") (pintype "passive"))
      (node (ref "C11") (pin "2") (pinfunction "2_2") (pintype "passive"))
      (node (ref "C12") (pin "2") (pinfunction "2_2") (pintype "passive"))
      (node (ref "C19") (pin "2") (pinfunction "2_2") (pintype "passive"))
      (node (ref "C2") (pin "2") (pinfunction "2_2") (pintype "passive"))
      (node (ref "C20") (pin "2") (pinfunction "2_2") (pintype "passive"))
      (node (ref "C21") (pin "2") (pinfunction "2_2") (pintype "passive"))
      (node (ref "C22") (pin "2") (pinfunction "2_2") (pintype "passive"))
      (node (ref "C23") (pin "2") (pinfunction "2_2") (pintype "passive"))
      (node (ref "C24") (pin "2") (pinfunction "2_2") (pintype "passive"))
      (node (ref "C25") (pin "2") (pinfunction "2_2") (pintype "passive"))
      (node (ref "C26") (pin "2") (pinfunction "2_2") (pintype "passive"))
      (node (ref "C27") (pin "2") (pinfunction "2_2") (pintype "passive"))
      (node (ref "C28") (pin "2") (pinfunction "2_2") (pintype "passive"))
      (node (ref "C29") (pin "2") (pinfunction "2_2") (pintype "passive"))
      (node (ref "C3") (pin "2") (pinfunction "2_2") (pintype "passive"))
      (node (ref "C30") (pin "2") (pinfunction "2_2") (pintype "passive"))
      (node (ref "C31") (pin "2") (pinfunction "2_2") (pintype "passive"))
      (node (ref "C32") (pin "2") (pinfunction "2_2") (pintype "passive"))
      (node (ref "C4") (pin "2") (pinfunction "2_2") (pintype "passive"))
      (node (ref "C5") (pin "1") (pinfunction "1_1") (pintype "passive"))
      (node (ref "C50") (pin "1") (pinfunction "1_1") (pintype "passive"))
      (node (ref "C51") (pin "1") (pinfunction "1_1") (pintype "passive"))
      (node (ref "C52") (pin "1") (pinfunction "1_1") (pintype "passive"))
      (node (ref "C55") (pin "2") (pinfunction "2_2") (pintype "passive"))
      (node (ref "C6") (pin "2") (pinfunction "2_2") (pintype "passive"))
      (node (ref "C8") (pin "1") (pinfunction "1_1") (pintype "passive"))
      (node (ref "C9") (pin "1") (pinfunction "1_1") (pintype "passive"))
      (node (ref "J1") (pin "5") (pinfunction "GND_5") (pintype "passive"))
      (node (ref "Q2") (pin "1") (pinfunction "S_1") (pintype "passive"))
      (node (ref "R10") (pin "1") (pinfunction "1_1") (pintype "passive"))
      (node (ref "R14") (pin "1") (pinfunction "1_1") (pintype "passive"))
      (node (ref "R15") (pin "1") (pinfunction "1_1") (pintype "passive"))
      (node (ref "R16") (pin "1") (pinfunction "1_1") (pintype "passive"))
      (node (ref "R26") (pin "1") (pinfunction "1_1") (pintype "passive"))
      (node (ref "R27") (pin "1") (pinfunction "1_1") (pintype "passive"))
      (node (ref "R28") (pin "1") (pinfunction "1_1") (pintype "passive"))
      (node (ref "R29") (pin "2") (pinfunction "2_2") (pintype "passive"))
      (node (ref "R3") (pin "2") (pinfunction "2_2") (pintype "passive"))
      (node (ref "R4") (pin "2") (pinfunction "2_2") (pintype "passive"))
      (node (ref "R9") (pin "1") (pinfunction "1_1") (pintype "passive"))
      (node (ref "ST1") (pin "1") (pinfunction "H1_1") (pintype "passive"))
      (node (ref "ST2") (pin "1") (pinfunction "H1_1") (pintype "passive"))
      (node (ref "ST3") (pin "1") (pinfunction "H1_1") (pintype "passive"))
      (node (ref "ST4") (pin "1") (pinfunction "H1_1") (pintype "passive"))
      (node (ref "U1") (pin "13") (pinfunction "TPAD_13") (pintype "passive"))
      (node (ref "U1") (pin "3") (pinfunction "VSS_3") (pintype "passive"))
      (node (ref "U10") (pin "11") (pinfunction "PP_11") (pintype "power_in"))
      (node (ref "U10") (pin "3") (pinfunction "PGND_3") (pintype "power_in"))
      (node (ref "U10") (pin "9") (pinfunction "GND_9") (pintype "power_in"))
      (node (ref "U2") (pin "11") (pinfunction "TPAD_11") (pintype "passive"))
      (node (ref "U2") (pin "3") (pinfunction "VSS_3") (pintype "passive"))
      (node (ref "U3") (pin "1") (pinfunction "PGND_1") (pintype "power_in"))
      (node (ref "U3") (pin "20") (pinfunction "PGND_20") (pintype "power_in"))
      (node (ref "U3") (pin "21") (pinfunction "EP_21") (pintype "passive"))
      (node (ref "U5") (pin "32") (pinfunction "VSSRF_32") (pintype "power_in"))
      (node (ref "U5") (pin "42") (pinfunction "VSSSMPS_42") (pintype "power_in"))
    )
    (net (code "25") (name "Net-(C61-Pad1)") (class "Default")
      (node (ref "C61") (pin "1") (pinfunction "1_1") (pintype "passive"))
      (node (ref "C62") (pin "1") (pinfunction "1_1") (pintype "passive"))
      (node (ref "C63") (pin "1") (pinfunction "1_1") (pintype "passive"))
      (node (ref "P2") (pin "2") (pinfunction "2_2") (pintype "passive"))
    )
    (net (code "26") (name "Net-(DS1-A)") (class "Default")
      (node (ref "DS1") (pin "1") (pinfunction "A_1") (pintype "passive"))
      (node (ref "R5") (pin "2") (pinfunction "2_2") (pintype "passive"))
    )
    (net (code "27") (name "Net-(DS1-K)") (class "Default")
      (node (ref "DS1") (pin "2") (pinfunction "K_2") (pintype "passive"))
      (node (ref "U2") (pin "5") (pinfunction "PG#_5") (pintype "passive"))
    )
    (net (code "28") (name "Net-(DS2-A)") (class "Default")
      (node (ref "DS2") (pin "1") (pinfunction "A_1") (pintype "passive"))
      (node (ref "R7") (pin "1") (pinfunction "1_1") (pintype "passive"))
    )
    (net (code "29") (name "Net-(DS3-A)") (class "Default")
      (node (ref "DS3") (pin "1") (pinfunction "A_1") (pintype "passive"))
      (node (ref "R8") (pin "1") (pinfunction "1_1") (pintype "passive"))
    )
    (net (code "30") (name "Net-(J1-VBUS)") (class "Default")
      (node (ref "C5") (pin "2") (pinfunction "2_2") (pintype "passive"))
      (node (ref "C6") (pin "1") (pinfunction "1_1") (pintype "passive"))
      (node (ref "J1") (pin "1") (pinfunction "VBUS_1") (pintype "passive"))
      (node (ref "Q1") (pin "1") (pinfunction "DRAIN_1") (pintype "passive"))
      (node (ref "Q1") (pin "2") (pinfunction "DRAIN_2") (pintype "passive"))
      (node (ref "Q1") (pin "5") (pinfunction "DRAIN_5") (pintype "passive"))
      (node (ref "Q1") (pin "6") (pinfunction "DRAIN_6") (pintype "passive"))
      (node (ref "U3") (pin "9") (pinfunction "AD_9") (pintype "passive"))
    )
    (net (code "31") (name "Net-(L1-Pad1)") (class "Default")
      (node (ref "L1") (pin "1") (pinfunction "1_1") (pintype "passive"))
      (node (ref "L2") (pin "2") (pinfunction "2_2") (pintype "passive"))
    )
    (net (code "32") (name "Net-(Q1-GATE)") (class "Default")
      (node (ref "Q1") (pin "3") (pinfunction "GATE_3") (pintype "passive"))
      (node (ref "U3") (pin "8") (pinfunction "~{AD-EN}_8") (pintype "passive"))
    )
    (net (code "33") (name "Net-(Q2A-D-Pad3)") (class "Default")
      (node (ref "Q2") (pin "3") (pinfunction "D_3") (pintype "passive"))
      (node (ref "Q2") (pin "6") (pinfunction "D_6") (pintype "passive"))
      (node (ref "Q2") (pin "7") (pinfunction "D_7") (pintype "passive"))
      (node (ref "Q2") (pin "8") (pinfunction "D_8") (pintype "passive"))
    )
    (net (code "34") (name "Net-(U1-PROG)") (class "Default")
      (node (ref "R3") (pin "1") (pinfunction "1_1") (pintype "passive"))
      (node (ref "U1") (pin "12") (pinfunction "PROG_12") (pintype "passive"))
    )
    (net (code "35") (name "Net-(U1-TEST)") (class "Default")
      (node (ref "R4") (pin "1") (pinfunction "1_1") (pintype "passive"))
      (node (ref "U1") (pin "10") (pinfunction "TEST_10") (pintype "passive"))
    )
    (net (code "36") (name "Net-(U1-VDD)") (class "Default")
      (node (ref "C3") (pin "1") (pinfunction "1_1") (pintype "passive"))
      (node (ref "U1") (pin "5") (pinfunction "VDD_5") (pintype "passive"))
    )
    (net (code "37") (name "Net-(U2-ISET)") (class "Default")
      (node (ref "R9") (pin "2") (pinfunction "2_2") (pintype "passive"))
      (node (ref "U2") (pin "2") (pinfunction "ISET_2") (pintype "passive"))
    )
    (net (code "38") (name "Net-(U2-NC)") (class "Default")
      (node (ref "R29") (pin "1") (pinfunction "1_1") (pintype "passive"))
      (node (ref "U2") (pin "6") (pinfunction "NC_6") (pintype "passive"))
    )
    (net (code "39") (name "Net-(U2-PRETERM)") (class "Default")
      (node (ref "R10") (pin "2") (pinfunction "2_2") (pintype "passive"))
      (node (ref "U2") (pin "4") (pinfunction "PRETERM_4") (pintype "passive"))
    )
    (net (code "40") (name "Net-(U3-FOD)") (class "Default")
      (node (ref "R12") (pin "2") (pinfunction "2_2") (pintype "passive"))
      (node (ref "R13") (pin "1") (pinfunction "1_1") (pintype "passive"))
      (node (ref "R16") (pin "2") (pinfunction "2_2") (pintype "passive"))
      (node (ref "U3") (pin "14") (pinfunction "FOD_14") (pintype "passive"))
    )
    (net (code "41") (name "Net-(U3-ILIM)") (class "Default")
      (node (ref "R12") (pin "1") (pinfunction "1_1") (pintype "passive"))
      (node (ref "U3") (pin "12") (pinfunction "ILIM_12") (pintype "passive"))
    )
    (net (code "42") (name "Net-(U3-RECT)") (class "Default")
      (node (ref "C10") (pin "1") (pinfunction "1_1") (pintype "passive"))
      (node (ref "C8") (pin "2") (pinfunction "2_2") (pintype "passive"))
      (node (ref "C9") (pin "2") (pinfunction "2_2") (pintype "passive"))
      (node (ref "R13") (pin "2") (pinfunction "2_2") (pintype "passive"))
      (node (ref "U3") (pin "18") (pinfunction "RECT_18") (pintype "passive"))
    )
    (net (code "43") (name "Net-(U3-TERM)") (class "Default")
      (node (ref "R15") (pin "2") (pinfunction "2_2") (pintype "passive"))
      (node (ref "U3") (pin "10") (pinfunction "TERM_10") (pintype "passive"))
    )
    (net (code "44") (name "Net-(U4-BAT)") (class "Default")
      (node (ref "C14") (pin "1") (pinfunction "1_1") (pintype "passive"))
      (node (ref "R11") (pin "1") (pinfunction "1_1") (pintype "passive"))
      (node (ref "U4") (pin "5") (pinfunction "BAT_5") (pintype "passive"))
    )
    (net (code "45") (name "Net-(U4-V-)") (class "Default")
      (node (ref "R14") (pin "2") (pinfunction "2_2") (pintype "passive"))
      (node (ref "U4") (pin "6") (pinfunction "V-_6") (pintype "passive"))
    )
    (net (code "46") (name "Net-(U5B-VFBSMPS)") (class "Default")
      (node (ref "C27") (pin "1") (pinfunction "1_1") (pintype "passive"))
      (node (ref "L2") (pin "1") (pinfunction "1_1") (pintype "passive"))
      (node (ref "U5") (pin "41") (pinfunction "VFBSMPS_41") (pintype "power_in"))
    )
    (net (code "47") (name "Net-(U5B-VLXSMPS)") (class "Default")
      (node (ref "L1") (pin "2") (pinfunction "2_2") (pintype "passive"))
      (node (ref "U5") (pin "43") (pinfunction "VLXSMPS_43") (pintype "power_in"))
    )
    (net (code "48") (name "Net-(U10-EN)") (class "Default")
      (node (ref "C55") (pin "1") (pinfunction "1_1") (pintype "passive"))
      (node (ref "R17") (pin "1") (pinfunction "1_1") (pintype "passive"))
      (node (ref "U10") (pin "6") (pinfunction "EN_6") (pintype "passive"))
      (node (ref "U10") (pin "7") (pinfunction "PS/SYNC_7") (pintype "passive"))
      (node (ref "U10") (pin "8") (pinfunction "VINA_8") (pintype "power_in"))
    )
    (net (code "49") (name "Net-(U10-L1)") (class "Default")
      (node (ref "L3") (pin "1") (pinfunction "1_1") (pintype "passive"))
      (node (ref "U10") (pin "4") (pinfunction "L1_4") (pintype "passive"))
    )
    (net (code "50") (name "Net-(U10-L2)") (class "Default")
      (node (ref "L3") (pin "2") (pinfunction "2_2") (pintype "passive"))
      (node (ref "U10") (pin "2") (pinfunction "L2_2") (pintype "passive"))
    )
    (net (code "51") (name "unconnected-(J1-D+-Pad3)") (class "Default")
      (node (ref "J1") (pin "3") (pinfunction "D+_3") (pintype "passive"))
    )
    (net (code "52") (name "unconnected-(J1-D--Pad2)") (class "Default")
      (node (ref "J1") (pin "2") (pinfunction "D-_2") (pintype "passive"))
    )
    (net (code "53") (name "unconnected-(J1-ID-Pad4)") (class "Default")
      (node (ref "J1") (pin "4") (pinfunction "ID_4") (pintype "passive"))
    )
    (net (code "54") (name "unconnected-(J1-SHLD1-Pad6)") (class "Default")
      (node (ref "J1") (pin "6") (pinfunction "SHLD1_6") (pintype "passive"))
    )
    (net (code "55") (name "unconnected-(J1-SHLD2-Pad7)") (class "Default")
      (node (ref "J1") (pin "7") (pinfunction "SHLD2_7") (pintype "passive"))
    )
    (net (code "56") (name "unconnected-(J1-SHLD3-Pad8)") (class "Default")
      (node (ref "J1") (pin "8") (pinfunction "SHLD3_8") (pintype "passive"))
    )
    (net (code "57") (name "unconnected-(J1-SHLD4-Pad9)") (class "Default")
      (node (ref "J1") (pin "9") (pinfunction "SHLD4_9") (pintype "passive"))
    )
    (net (code "58") (name "unconnected-(U1-NC-Pad4)") (class "Default")
      (node (ref "U1") (pin "4") (pinfunction "NC_4") (pintype "passive"))
    )
    (net (code "59") (name "unconnected-(U1-NC-Pad9)") (class "Default")
      (node (ref "U1") (pin "9") (pinfunction "NC_9") (pintype "passive"))
    )
    (net (code "60") (name "unconnected-(U1-NC-Pad11)") (class "Default")
      (node (ref "U1") (pin "11") (pinfunction "NC_11") (pintype "passive"))
    )
    (net (code "61") (name "unconnected-(U2-TS-Pad9)") (class "Default")
      (node (ref "U2") (pin "9") (pinfunction "TS_9") (pintype "passive"))
    )
    (net (code "62") (name "unconnected-(U4-NC-Pad1)") (class "Default")
      (node (ref "U4") (pin "1") (pinfunction "NC_1") (pintype "passive"))
    )
  )
)
